# ledlights.net
KiCad netlist of a schematic drawn in EAGLE
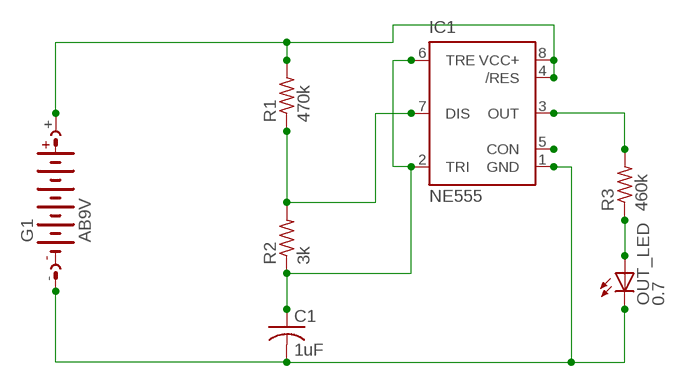
[diagram p0: schematic, sheet 1]

(export (version "E")
  (design (tool "Eeschema 10.0.6"))
  (components
    (comp (ref "C1")
      (value "1uF")
      (footprint "eagle-import:C0805")
      (libsource (lib "eagle-import") (part "C-USC0805"))
    )
    (comp (ref "G1")
      (value "AB9V")
      (footprint "eagle-import:AB9V")
      (libsource (lib "eagle-import") (part "AB9V"))
    )
    (comp (ref "IC1")
      (value "NE555")
      (footprint "eagle-import:DIL-08")
      (fields (field (name "MF") "Arrow Electronics") (field (name "MPN") "NE555N"))
      (libsource (lib "eagle-import") (part "NE555"))
    )
    (comp (ref "OUT_LED")
      (value "0.7")
      (footprint "eagle-import:CHIP-LED0805")
      (libsource (lib "eagle-import") (part "LEDCHIP-LED0805"))
    )
    (comp (ref "R1")
      (value "470k")
      (footprint "eagle-import:R0805")
      (libsource (lib "eagle-import") (part "R-US_R0805"))
    )
    (comp (ref "R2")
      (value "3k")
      (footprint "eagle-import:R0805")
      (libsource (lib "eagle-import") (part "R-US_R0805"))
    )
    (comp (ref "R3")
      (value "460k")
      (footprint "eagle-import:R0805")
      (libsource (lib "eagle-import") (part "R-US_R0805"))
    )
  )
  (nets
    (net (code "1") (name "Net-(IC1-DIS)") (class "Default")
      (node (ref "IC1") (pin "7") (pinfunction "DIS_7") (pintype "input"))
      (node (ref "R1") (pin "1") (pinfunction "1_1") (pintype "passive"))
      (node (ref "R2") (pin "2") (pinfunction "2_2") (pintype "passive"))
    )
    (net (code "2") (name "Net-(IC1-GND)") (class "Default")
      (node (ref "C1") (pin "2") (pinfunction "2_2") (pintype "passive"))
      (node (ref "G1") (pin "-") (pinfunction "-_-") (pintype "passive"))
      (node (ref "IC1") (pin "1") (pinfunction "GND_1") (pintype "power_in"))
      (node (ref "OUT_LED") (pin "C") (pinfunction "C_C") (pintype "passive"))
    )
    (net (code "3") (name "Net-(IC1-OUT)") (class "Default")
      (node (ref "IC1") (pin "3") (pinfunction "OUT_3") (pintype "output"))
      (node (ref "R3") (pin "2") (pinfunction "2_2") (pintype "passive"))
    )
    (net (code "4") (name "Net-(IC1-TRE)") (class "Default")
      (node (ref "C1") (pin "1") (pinfunction "1_1") (pintype "passive"))
      (node (ref "IC1") (pin "2") (pinfunction "TRI_2") (pintype "input"))
      (node (ref "IC1") (pin "6") (pinfunction "TRE_6") (pintype "input"))
      (node (ref "R2") (pin "1") (pinfunction "1_1") (pintype "passive"))
    )
    (net (code "5") (name "Net-(IC1-VCC+)") (class "Default")
      (node (ref "G1") (pin "+") (pinfunction "+_+") (pintype "passive"))
      (node (ref "IC1") (pin "4") (pinfunction "/RES_4") (pintype "input"))
      (node (ref "IC1") (pin "8") (pinfunction "VCC+_8") (pintype "power_in"))
      (node (ref "R1") (pin "2") (pinfunction "2_2") (pintype "passive"))
    )
    (net (code "6") (name "Net-(OUT_LED-PadA)") (class "Default")
      (node (ref "OUT_LED") (pin "A") (pinfunction "A_A") (pintype "passive"))
      (node (ref "R3") (pin "1") (pinfunction "1_1") (pintype "passive"))
    )
    (net (code "7") (name "unconnected-(IC1-CON-Pad5)") (class "Default")
      (node (ref "IC1") (pin "5") (pinfunction "CON_5") (pintype "input"))
    )
  )
)
